# usb.net
KiCad netlist of a schematic drawn in Altium Designer
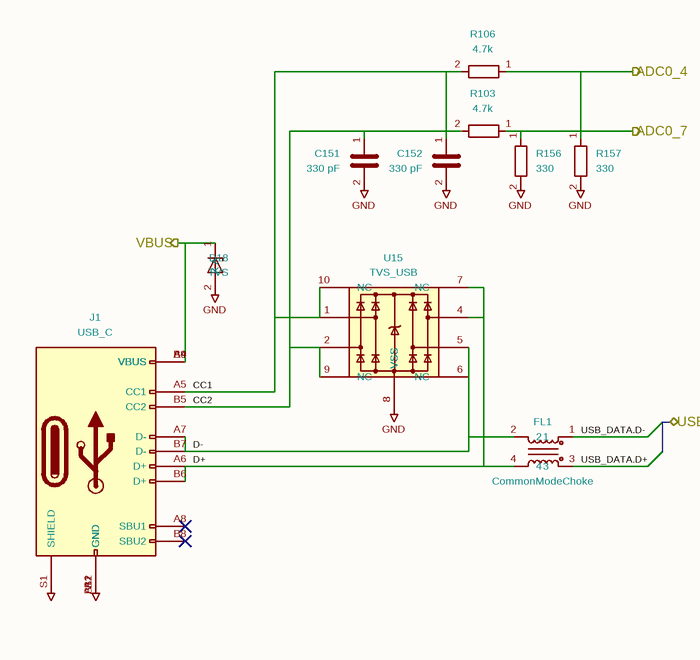
[diagram p0: usb.SchDoc]

(export (version "E")
  (design (tool "Eeschema 10.0.6"))
  (components
    (comp (ref "C151")
      (value "330 pF")
      (footprint "C_0201_0603Metric")
      (description "CAP CER 330PF 25V C0G/NP0 0201")
      (fields (field (name "PART NUMBER") "GRM0335C1E331JA01D") (field (name "MANUFACTURER") "Murata"))
      (libsource (lib "Device") (part "C"))
    )
    (comp (ref "C152")
      (value "330 pF")
      (footprint "C_0201_0603Metric")
      (description "CAP CER 330PF 25V C0G/NP0 0201")
      (fields (field (name "PART NUMBER") "GRM0335C1E331JA01D") (field (name "MANUFACTURER") "Murata"))
      (libsource (lib "Device") (part "C"))
    )
    (comp (ref "D18")
      (value "TVS")
      (footprint "TSLP-2-19")
      (description "TVS DIODE 12V UNIDIRECTIONAL DFN1006")
      (fields (field (name "MANUFACTURER") "MDD") (field (name "PART NUMBER") "ESD8D12V"))
      (libsource (lib "Device") (part "D_Zener"))
    )
    (comp (ref "FL1")
      (value "CommonModeChoke")
      (footprint "L_CommonModeChoke_Murata_DLM0NS")
      (description "CMC 130MA 2LN 28 OHM SMD")
      (fields (field (name "MANUFACTURER") "Murata") (field (name "PART NUMBER") "DLM0NSB280HY2D"))
      (libsource (lib "Device") (part "Filter_EMI_CommonMode"))
    )
    (comp (ref "J1")
      (value "USB_C")
      (footprint "USB_C_Receptacle_HRO_TYPE-C-31-M-12")
      (description "CONN RCPT USB2.0 TYPE-C 16POS")
      (fields (field (name "MANUFACTURER") "DEALON") (field (name "PART NUMBER") "USB-TYPE-C-019"))
      (libsource (lib "Connector") (part "USB_C_Receptacle_USB2.0_16P"))
    )
    (comp (ref "R103")
      (value "4.7k")
      (footprint "R_0201_0603Metric")
      (description "RES 4.7K OHM 1% 1/20W 0201")
      (fields (field (name "MANUFACTURER") "Yageo") (field (name "PART NUMBER") "RC0201FR-074K7L"))
      (libsource (lib "") (part "R_1"))
    )
    (comp (ref "R106")
      (value "4.7k")
      (footprint "R_0201_0603Metric")
      (description "RES 4.7K OHM 1% 1/20W 0201")
      (fields (field (name "MANUFACTURER") "Yageo") (field (name "PART NUMBER") "RC0201FR-074K7L"))
      (libsource (lib "") (part "R_1"))
    )
    (comp (ref "R156")
      (value "330")
      (footprint "R_0201_0603Metric")
      (description "RES 330 OHM 5% 1/20W 0201")
      (fields (field (name "MANUFACTURER") "Yageo") (field (name "PART NUMBER") "RC0201JR-07330RL"))
      (libsource (lib "Device") (part "R"))
    )
    (comp (ref "R157")
      (value "330")
      (footprint "R_0201_0603Metric")
      (description "RES 330 OHM 5% 1/20W 0201")
      (fields (field (name "MANUFACTURER") "Yageo") (field (name "PART NUMBER") "RC0201JR-07330RL"))
      (libsource (lib "Device") (part "R"))
    )
    (comp (ref "U15")
      (value "TVS_USB")
      (footprint "Diodes_UDFN-10_1.0x2.5mm_P0.5mm")
      (description "4-Channel Low Capacitance TVS Diode Array, DFN-10")
      (fields (field (name "MANUFACTURER") "TECH PUBLIC") (field (name "PART NUMBER") "TPAZ1143-04F"))
      (libsource (lib "Power_Protection") (part "D3V3XA4B10LP"))
    )
  )
  (nets
    (net (code "2") (name "/ADC0_4") (class "Default")
      (node (ref "R106") (pin "1") (pinfunction "1_1") (pintype "passive"))
      (node (ref "R157") (pin "1") (pinfunction "1_1") (pintype "passive"))
    )
    (net (code "3") (name "/ADC0_7") (class "Default")
      (node (ref "R103") (pin "1") (pinfunction "1_1") (pintype "passive"))
      (node (ref "R156") (pin "1") (pinfunction "1_1") (pintype "passive"))
    )
    (net (code "4") (name "/CC1") (class "Default")
      (node (ref "C152") (pin "1") (pinfunction "1_1") (pintype "passive"))
      (node (ref "J1") (pin "A5") (pinfunction "CC1_A5") (pintype "passive"))
      (node (ref "R106") (pin "2") (pinfunction "2_2") (pintype "passive"))
      (node (ref "U15") (pin "1") (pinfunction "1_1") (pintype "passive"))
      (node (ref "U15") (pin "10") (pinfunction "NC_10") (pintype "passive"))
    )
    (net (code "5") (name "/CC2") (class "Default")
      (node (ref "C151") (pin "1") (pinfunction "1_1") (pintype "passive"))
      (node (ref "J1") (pin "B5") (pinfunction "CC2_B5") (pintype "passive"))
      (node (ref "R103") (pin "2") (pinfunction "2_2") (pintype "passive"))
      (node (ref "U15") (pin "2") (pinfunction "2_2") (pintype "passive"))
      (node (ref "U15") (pin "9") (pinfunction "NC_9") (pintype "passive"))
    )
    (net (code "6") (name "/D+") (class "Default")
      (node (ref "FL1") (pin "4") (pinfunction "4_4") (pintype "passive"))
      (node (ref "J1") (pin "A6") (pinfunction "D+_A6") (pintype "passive"))
      (node (ref "J1") (pin "B6") (pinfunction "D+_B6") (pintype "passive"))
      (node (ref "U15") (pin "4") (pinfunction "4_4") (pintype "passive"))
      (node (ref "U15") (pin "7") (pinfunction "NC_7") (pintype "passive"))
    )
    (net (code "7") (name "/D-") (class "Default")
      (node (ref "FL1") (pin "2") (pinfunction "2_2") (pintype "passive"))
      (node (ref "J1") (pin "A7") (pinfunction "D-_A7") (pintype "passive"))
      (node (ref "J1") (pin "B7") (pinfunction "D-_B7") (pintype "passive"))
      (node (ref "U15") (pin "5") (pinfunction "5_5") (pintype "passive"))
      (node (ref "U15") (pin "6") (pinfunction "NC_6") (pintype "passive"))
    )
    (net (code "8") (name "/USB_DATA.D+") (class "Default")
      (node (ref "FL1") (pin "3") (pinfunction "3_3") (pintype "passive"))
    )
    (net (code "9") (name "/USB_DATA.D-") (class "Default")
      (node (ref "FL1") (pin "1") (pinfunction "1_1") (pintype "passive"))
    )
    (net (code "11") (name "/VBUS") (class "Default")
      (node (ref "D18") (pin "1") (pinfunction "K_1") (pintype "passive"))
      (node (ref "J1") (pin "A4") (pinfunction "VBUS_A4") (pintype "passive"))
      (node (ref "J1") (pin "A9") (pinfunction "VBUS_A9") (pintype "passive"))
      (node (ref "J1") (pin "B4") (pinfunction "VBUS_B4") (pintype "passive"))
      (node (ref "J1") (pin "B9") (pinfunction "VBUS_B9") (pintype "passive"))
    )
    (net (code "12") (name "GND") (class "Default")
      (node (ref "C151") (pin "2") (pinfunction "2_2") (pintype "passive"))
      (node (ref "C152") (pin "2") (pinfunction "2_2") (pintype "passive"))
      (node (ref "D18") (pin "2") (pinfunction "A_2") (pintype "passive"))
      (node (ref "J1") (pin "A1") (pinfunction "GND_A1") (pintype "passive"))
      (node (ref "J1") (pin "A12") (pinfunction "GND_A12") (pintype "passive"))
      (node (ref "J1") (pin "B1") (pinfunction "GND_B1") (pintype "passive"))
      (node (ref "J1") (pin "B12") (pinfunction "GND_B12") (pintype "passive"))
      (node (ref "J1") (pin "S1") (pinfunction "SHIELD_S1") (pintype "passive"))
      (node (ref "R156") (pin "2") (pinfunction "2_2") (pintype "passive"))
      (node (ref "R157") (pin "2") (pinfunction "2_2") (pintype "passive"))
      (node (ref "U15") (pin "3") (pinfunction "VSS_3") (pintype "passive"))
      (node (ref "U15") (pin "8") (pinfunction "VSS_8") (pintype "passive"))
    )
    (net (code "13") (name "unconnected-(J1-SBU1-PadA8)") (class "Default")
      (node (ref "J1") (pin "A8") (pinfunction "SBU1_A8") (pintype "passive+no_connect"))
    )
    (net (code "14") (name "unconnected-(J1-SBU2-PadB8)") (class "Default")
      (node (ref "J1") (pin "B8") (pinfunction "SBU2_B8") (pintype "passive+no_connect"))
    )
  )
)
